# wrist_sch.net
KiCad netlist of a schematic drawn in Altium Designer
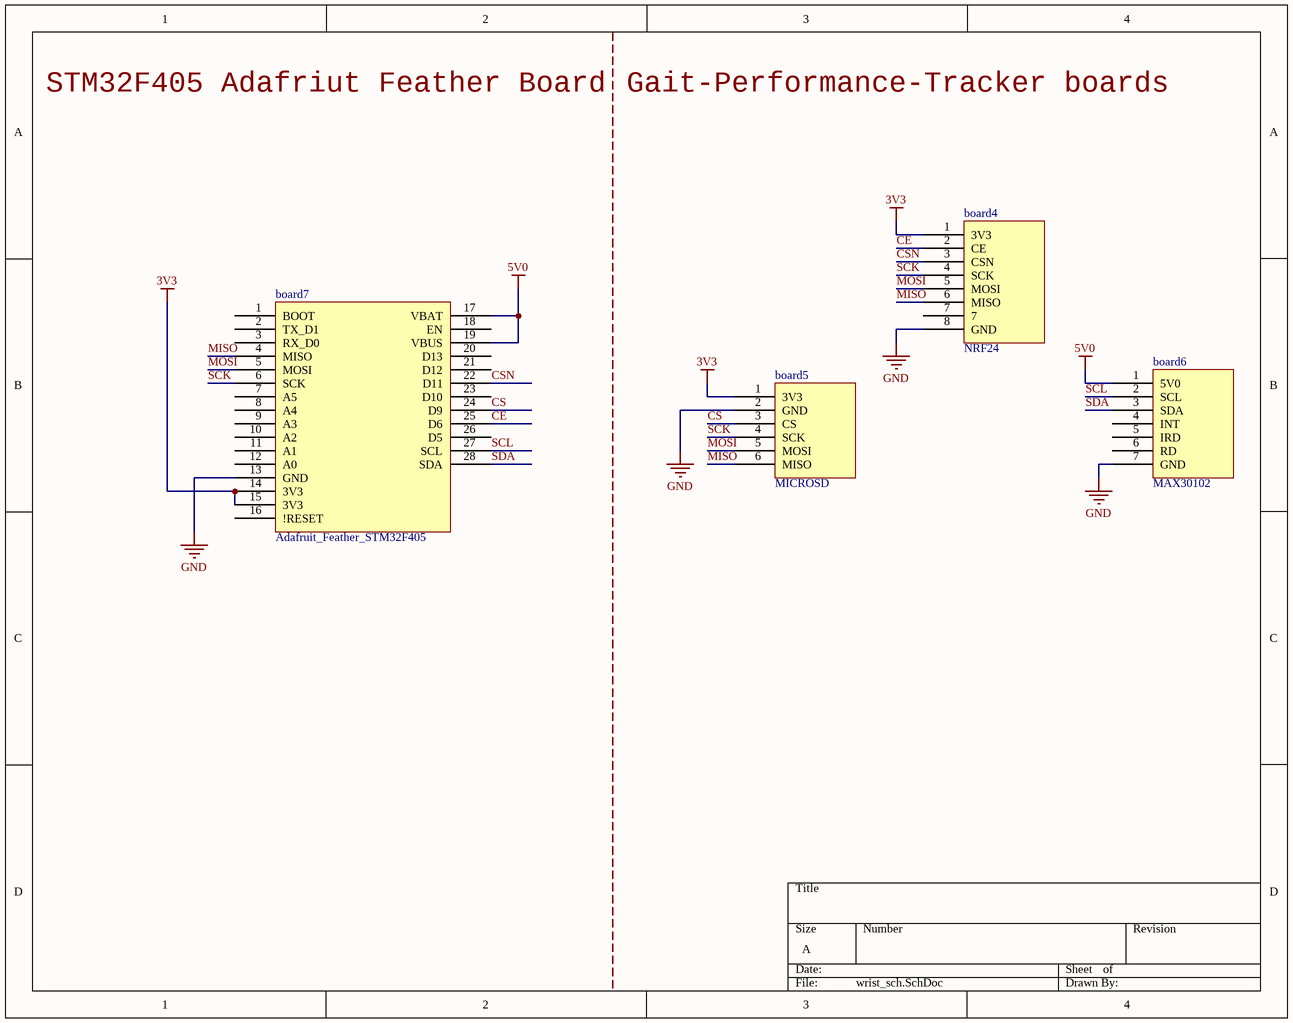
[diagram p0: wrist_sch.SchDoc]

(export (version "E")
  (design (tool "Eeschema 10.0.6"))
  (components
    (comp (ref "board4") (value "NRF24") (footprint "nrf24") (libsource (lib "Schlib1") (part "NRF24")))
    (comp (ref "board5")
      (value "MICROSD")
      (footprint "Model Name")
      (libsource (lib "Schlib1") (part "MICROSD"))
    )
    (comp (ref "board6")
      (value "MAX30102")
      (footprint "max30102")
      (libsource (lib "Schlib1") (part "MAX30102"))
    )
    (comp (ref "board7")
      (value "Adafruit_Feather_STM32F405")
      (footprint "Adafruit_Feather_STM32F405")
      (libsource (lib "Schlib1") (part "Adafruit_Feather_STM32F405"))
    )
  )
  (nets
    (net (code "1") (name "/CE") (class "Default")
      (node (ref "board4") (pin "2") (pinfunction "CE_2") (pintype "passive"))
      (node (ref "board7") (pin "25") (pinfunction "D6_25") (pintype "passive"))
    )
    (net (code "2") (name "/CS") (class "Default")
      (node (ref "board5") (pin "3") (pinfunction "CS_3") (pintype "passive"))
      (node (ref "board7") (pin "24") (pinfunction "D9_24") (pintype "passive"))
    )
    (net (code "3") (name "/CSN") (class "Default")
      (node (ref "board4") (pin "3") (pinfunction "CSN_3") (pintype "passive"))
      (node (ref "board7") (pin "22") (pinfunction "D11_22") (pintype "passive"))
    )
    (net (code "4") (name "/MISO") (class "Default")
      (node (ref "board4") (pin "6") (pinfunction "MISO_6") (pintype "passive"))
      (node (ref "board5") (pin "6") (pinfunction "MISO_6") (pintype "passive"))
      (node (ref "board7") (pin "4") (pinfunction "MISO_4") (pintype "passive"))
    )
    (net (code "5") (name "/MOSI") (class "Default")
      (node (ref "board4") (pin "5") (pinfunction "MOSI_5") (pintype "passive"))
      (node (ref "board5") (pin "5") (pinfunction "MOSI_5") (pintype "passive"))
      (node (ref "board7") (pin "5") (pinfunction "MOSI_5") (pintype "passive"))
    )
    (net (code "6") (name "/SCK") (class "Default")
      (node (ref "board4") (pin "4") (pinfunction "SCK_4") (pintype "passive"))
      (node (ref "board5") (pin "4") (pinfunction "SCK_4") (pintype "passive"))
      (node (ref "board7") (pin "6") (pinfunction "SCK_6") (pintype "passive"))
    )
    (net (code "7") (name "/SCL") (class "Default")
      (node (ref "board6") (pin "2") (pinfunction "SCL_2") (pintype "passive"))
      (node (ref "board7") (pin "27") (pinfunction "SCL_27") (pintype "passive"))
    )
    (net (code "8") (name "/SDA") (class "Default")
      (node (ref "board6") (pin "3") (pinfunction "SDA_3") (pintype "passive"))
      (node (ref "board7") (pin "28") (pinfunction "SDA_28") (pintype "passive"))
    )
    (net (code "9") (name "3V3") (class "Default")
      (node (ref "board4") (pin "1") (pinfunction "3V3_1") (pintype "passive"))
      (node (ref "board5") (pin "1") (pinfunction "3V3_1") (pintype "passive"))
      (node (ref "board7") (pin "14") (pinfunction "3V3_14") (pintype "passive"))
      (node (ref "board7") (pin "15") (pinfunction "3V3_15") (pintype "passive"))
    )
    (net (code "10") (name "5V0") (class "Default")
      (node (ref "board6") (pin "1") (pinfunction "5V0_1") (pintype "passive"))
      (node (ref "board7") (pin "17") (pinfunction "VBAT_17") (pintype "passive"))
      (node (ref "board7") (pin "19") (pinfunction "VBUS_19") (pintype "passive"))
    )
    (net (code "11") (name "GND") (class "Default")
      (node (ref "board4") (pin "8") (pinfunction "GND_8") (pintype "passive"))
      (node (ref "board5") (pin "2") (pinfunction "GND_2") (pintype "passive"))
      (node (ref "board6") (pin "7") (pinfunction "GND_7") (pintype "passive"))
      (node (ref "board7") (pin "13") (pinfunction "GND_13") (pintype "passive"))
    )
    (net (code "12") (name "unconnected-(board4-Pad7)") (class "Default")
      (node (ref "board4") (pin "7") (pinfunction "7_7") (pintype "passive"))
    )
    (net (code "13") (name "unconnected-(board6-INT-Pad4)") (class "Default")
      (node (ref "board6") (pin "4") (pinfunction "INT_4") (pintype "passive"))
    )
    (net (code "14") (name "unconnected-(board6-IRD-Pad5)") (class "Default")
      (node (ref "board6") (pin "5") (pinfunction "IRD_5") (pintype "passive"))
    )
    (net (code "15") (name "unconnected-(board6-RD-Pad6)") (class "Default")
      (node (ref "board6") (pin "6") (pinfunction "RD_6") (pintype "passive"))
    )
    (net (code "16") (name "unconnected-(board7-!RESET-Pad16)") (class "Default")
      (node (ref "board7") (pin "16") (pinfunction "!RESET_16") (pintype "passive"))
    )
    (net (code "17") (name "unconnected-(board7-A0-Pad12)") (class "Default")
      (node (ref "board7") (pin "12") (pinfunction "A0_12") (pintype "passive"))
    )
    (net (code "18") (name "unconnected-(board7-A1-Pad11)") (class "Default")
      (node (ref "board7") (pin "11") (pinfunction "A1_11") (pintype "passive"))
    )
    (net (code "19") (name "unconnected-(board7-A2-Pad10)") (class "Default")
      (node (ref "board7") (pin "10") (pinfunction "A2_10") (pintype "passive"))
    )
    (net (code "20") (name "unconnected-(board7-A3-Pad9)") (class "Default")
      (node (ref "board7") (pin "9") (pinfunction "A3_9") (pintype "passive"))
    )
    (net (code "21") (name "unconnected-(board7-A4-Pad8)") (class "Default")
      (node (ref "board7") (pin "8") (pinfunction "A4_8") (pintype "passive"))
    )
    (net (code "22") (name "unconnected-(board7-A5-Pad7)") (class "Default")
      (node (ref "board7") (pin "7") (pinfunction "A5_7") (pintype "passive"))
    )
    (net (code "23") (name "unconnected-(board7-BOOT-Pad1)") (class "Default")
      (node (ref "board7") (pin "1") (pinfunction "BOOT_1") (pintype "passive"))
    )
    (net (code "24") (name "unconnected-(board7-D5-Pad26)") (class "Default")
      (node (ref "board7") (pin "26") (pinfunction "D5_26") (pintype "passive"))
    )
    (net (code "25") (name "unconnected-(board7-D10-Pad23)") (class "Default")
      (node (ref "board7") (pin "23") (pinfunction "D10_23") (pintype "passive"))
    )
    (net (code "26") (name "unconnected-(board7-D12-Pad21)") (class "Default")
      (node (ref "board7") (pin "21") (pinfunction "D12_21") (pintype "passive"))
    )
    (net (code "27") (name "unconnected-(board7-D13-Pad20)") (class "Default")
      (node (ref "board7") (pin "20") (pinfunction "D13_20") (pintype "passive"))
    )
    (net (code "28") (name "unconnected-(board7-EN-Pad18)") (class "Default")
      (node (ref "board7") (pin "18") (pinfunction "EN_18") (pintype "passive"))
    )
    (net (code "29") (name "unconnected-(board7-RX_D0-Pad3)") (class "Default")
      (node (ref "board7") (pin "3") (pinfunction "RX_D0_3") (pintype "passive"))
    )
    (net (code "30") (name "unconnected-(board7-TX_D1-Pad2)") (class "Default")
      (node (ref "board7") (pin "2") (pinfunction "TX_D1_2") (pintype "passive"))
    )
  )
)
